# Sensor_Decoderv0_6.net
KiCad netlist of a schematic drawn in EAGLE
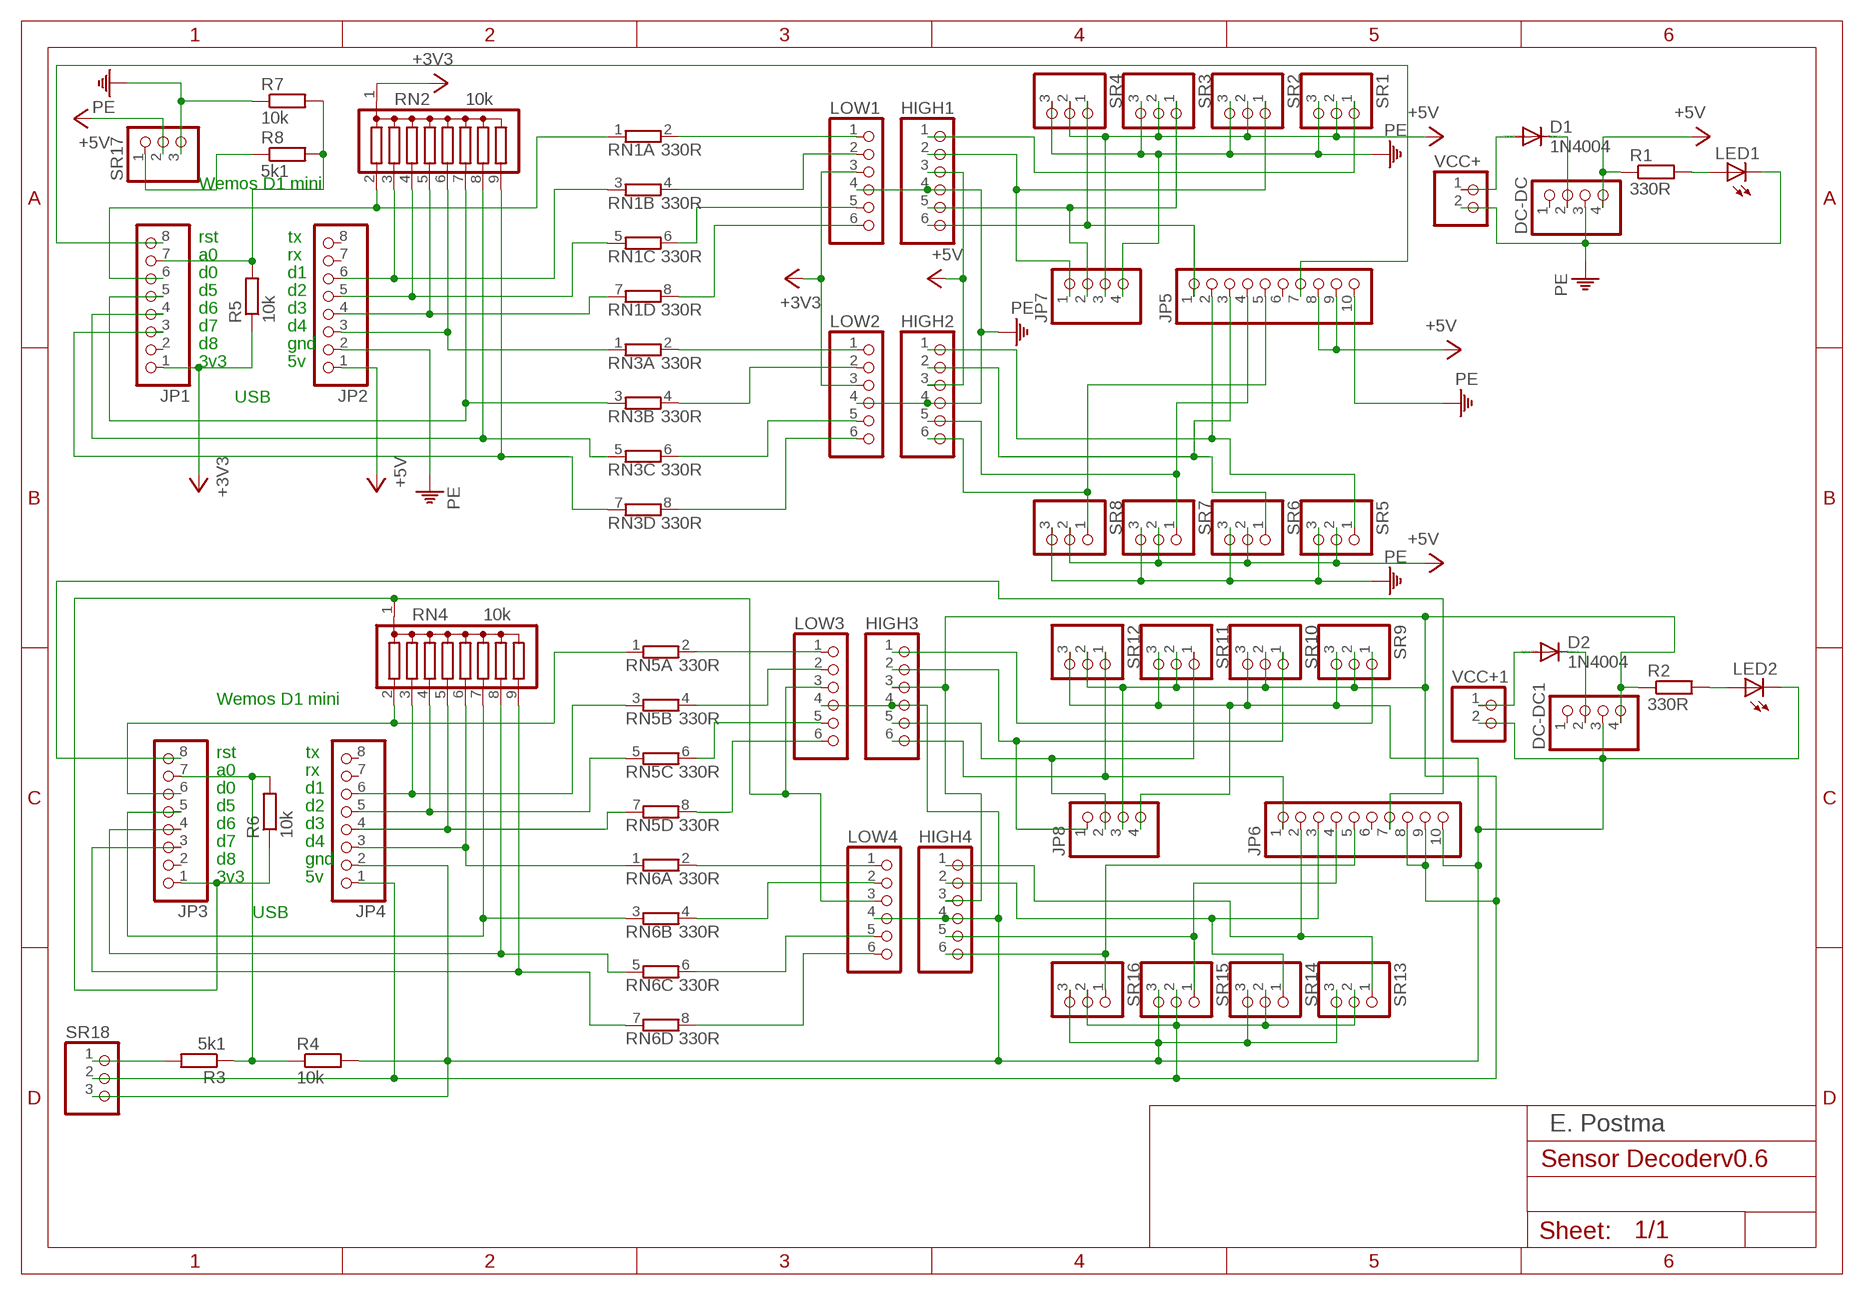
[diagram p0: schematic, sheet 1]

(export (version "E")
  (design (tool "Eeschema 10.0.6"))
  (components
    (comp (ref "D1")
      (value "1N4004")
      (footprint "eagle-import:DO41-10")
      (libsource (lib "eagle-import") (part "1N4004"))
    )
    (comp (ref "D2")
      (value "1N4004")
      (footprint "eagle-import:DO41-10")
      (libsource (lib "eagle-import") (part "1N4004"))
    )
    (comp (ref "DC-DC")
      (value "PINHD-1X4")
      (footprint "eagle-import:1X04")
      (libsource (lib "eagle-import") (part "PINHD-1X4"))
    )
    (comp (ref "DC-DC1")
      (value "PINHD-1X4")
      (footprint "eagle-import:1X04")
      (libsource (lib "eagle-import") (part "PINHD-1X4"))
    )
    (comp (ref "HIGH1")
      (value "PINHD-1X6")
      (footprint "eagle-import:1X06")
      (libsource (lib "eagle-import") (part "PINHD-1X6"))
    )
    (comp (ref "HIGH2")
      (value "PINHD-1X6")
      (footprint "eagle-import:1X06")
      (libsource (lib "eagle-import") (part "PINHD-1X6"))
    )
    (comp (ref "HIGH3")
      (value "PINHD-1X6")
      (footprint "eagle-import:1X06")
      (libsource (lib "eagle-import") (part "PINHD-1X6"))
    )
    (comp (ref "HIGH4")
      (value "PINHD-1X6")
      (footprint "eagle-import:1X06")
      (libsource (lib "eagle-import") (part "PINHD-1X6"))
    )
    (comp (ref "JP1")
      (value "PINHD-1X8")
      (footprint "eagle-import:1X08")
      (libsource (lib "eagle-import") (part "PINHD-1X8"))
    )
    (comp (ref "JP2")
      (value "PINHD-1X8")
      (footprint "eagle-import:1X08")
      (libsource (lib "eagle-import") (part "PINHD-1X8"))
    )
    (comp (ref "JP3")
      (value "PINHD-1X8")
      (footprint "eagle-import:1X08")
      (libsource (lib "eagle-import") (part "PINHD-1X8"))
    )
    (comp (ref "JP4")
      (value "PINHD-1X8")
      (footprint "eagle-import:1X08")
      (libsource (lib "eagle-import") (part "PINHD-1X8"))
    )
    (comp (ref "JP5")
      (value "PINHD-1X10")
      (footprint "eagle-import:1X10")
      (libsource (lib "eagle-import") (part "PINHD-1X10"))
    )
    (comp (ref "JP6")
      (value "PINHD-1X10")
      (footprint "eagle-import:1X10")
      (libsource (lib "eagle-import") (part "PINHD-1X10"))
    )
    (comp (ref "JP7")
      (value "PINHD-1X4")
      (footprint "eagle-import:1X04")
      (libsource (lib "eagle-import") (part "pinhead_325_PINHD-1X4"))
    )
    (comp (ref "JP8")
      (value "PINHD-1X4")
      (footprint "eagle-import:1X04")
      (libsource (lib "eagle-import") (part "pinhead_325_PINHD-1X4"))
    )
    (comp (ref "LED1")
      (value "LED3MM")
      (footprint "eagle-import:LED3MM")
      (libsource (lib "eagle-import") (part "LED3MM"))
    )
    (comp (ref "LED2")
      (value "LED3MM")
      (footprint "eagle-import:LED3MM")
      (libsource (lib "eagle-import") (part "LED3MM"))
    )
    (comp (ref "LOW1")
      (value "PINHD-1X6")
      (footprint "eagle-import:1X06")
      (libsource (lib "eagle-import") (part "PINHD-1X6"))
    )
    (comp (ref "LOW2")
      (value "PINHD-1X6")
      (footprint "eagle-import:1X06")
      (libsource (lib "eagle-import") (part "PINHD-1X6"))
    )
    (comp (ref "LOW3")
      (value "PINHD-1X6")
      (footprint "eagle-import:1X06")
      (libsource (lib "eagle-import") (part "PINHD-1X6"))
    )
    (comp (ref "LOW4")
      (value "PINHD-1X6")
      (footprint "eagle-import:1X06")
      (libsource (lib "eagle-import") (part "PINHD-1X6"))
    )
    (comp (ref "R1")
      (value "330R")
      (footprint "eagle-import:0207_7")
      (libsource (lib "eagle-import") (part "R-EU_0207/7"))
    )
    (comp (ref "R2")
      (value "330R")
      (footprint "eagle-import:0207_7")
      (libsource (lib "eagle-import") (part "R-EU_0207/7"))
    )
    (comp (ref "R3")
      (value "5k1")
      (footprint "eagle-import:0207_7")
      (libsource (lib "eagle-import") (part "R-EU_0207/7"))
    )
    (comp (ref "R4")
      (value "10k")
      (footprint "eagle-import:0207_7")
      (libsource (lib "eagle-import") (part "R-EU_0207/7"))
    )
    (comp (ref "R5")
      (value "10k")
      (footprint "eagle-import:0207_7")
      (libsource (lib "eagle-import") (part "R-EU_0207/7"))
    )
    (comp (ref "R6")
      (value "10k")
      (footprint "eagle-import:0207_7")
      (libsource (lib "eagle-import") (part "R-EU_0207/7"))
    )
    (comp (ref "R7")
      (value "10k")
      (footprint "eagle-import:0207_7")
      (libsource (lib "eagle-import") (part "R-EU_0207/7"))
    )
    (comp (ref "R8")
      (value "5k1")
      (footprint "eagle-import:0207_7")
      (libsource (lib "eagle-import") (part "R-EU_0207/7"))
    )
    (comp (ref "RN1")
      (value "330R")
      (footprint "eagle-import:SIL8")
      (libsource (lib "eagle-import") (part "E4R"))
    )
    (comp (ref "RN2")
      (value "10k")
      (footprint "eagle-import:SIL9")
      (libsource (lib "eagle-import") (part "G08R"))
    )
    (comp (ref "RN3")
      (value "330R")
      (footprint "eagle-import:SIL8")
      (libsource (lib "eagle-import") (part "E4R"))
    )
    (comp (ref "RN4")
      (value "10k")
      (footprint "eagle-import:SIL9")
      (libsource (lib "eagle-import") (part "G08R"))
    )
    (comp (ref "RN5")
      (value "330R")
      (footprint "eagle-import:SIL8")
      (libsource (lib "eagle-import") (part "E4R"))
    )
    (comp (ref "RN6")
      (value "330R")
      (footprint "eagle-import:SIL8")
      (libsource (lib "eagle-import") (part "E4R"))
    )
    (comp (ref "SR1")
      (value "PINHD-1X3")
      (footprint "eagle-import:1X03")
      (libsource (lib "eagle-import") (part "PINHD-1X3"))
    )
    (comp (ref "SR2")
      (value "PINHD-1X3")
      (footprint "eagle-import:1X03")
      (libsource (lib "eagle-import") (part "PINHD-1X3"))
    )
    (comp (ref "SR3")
      (value "PINHD-1X3")
      (footprint "eagle-import:1X03")
      (libsource (lib "eagle-import") (part "PINHD-1X3"))
    )
    (comp (ref "SR4")
      (value "PINHD-1X3")
      (footprint "eagle-import:1X03")
      (libsource (lib "eagle-import") (part "PINHD-1X3"))
    )
    (comp (ref "SR5")
      (value "PINHD-1X3")
      (footprint "eagle-import:1X03")
      (libsource (lib "eagle-import") (part "PINHD-1X3"))
    )
    (comp (ref "SR6")
      (value "PINHD-1X3")
      (footprint "eagle-import:1X03")
      (libsource (lib "eagle-import") (part "PINHD-1X3"))
    )
    (comp (ref "SR7")
      (value "PINHD-1X3")
      (footprint "eagle-import:1X03")
      (libsource (lib "eagle-import") (part "PINHD-1X3"))
    )
    (comp (ref "SR8")
      (value "PINHD-1X3")
      (footprint "eagle-import:1X03")
      (libsource (lib "eagle-import") (part "PINHD-1X3"))
    )
    (comp (ref "SR9")
      (value "PINHD-1X3")
      (footprint "eagle-import:1X03")
      (libsource (lib "eagle-import") (part "PINHD-1X3"))
    )
    (comp (ref "SR10")
      (value "PINHD-1X3")
      (footprint "eagle-import:1X03")
      (libsource (lib "eagle-import") (part "PINHD-1X3"))
    )
    (comp (ref "SR11")
      (value "PINHD-1X3")
      (footprint "eagle-import:1X03")
      (libsource (lib "eagle-import") (part "PINHD-1X3"))
    )
    (comp (ref "SR12")
      (value "PINHD-1X3")
      (footprint "eagle-import:1X03")
      (libsource (lib "eagle-import") (part "PINHD-1X3"))
    )
    (comp (ref "SR13")
      (value "PINHD-1X3")
      (footprint "eagle-import:1X03")
      (libsource (lib "eagle-import") (part "PINHD-1X3"))
    )
    (comp (ref "SR14")
      (value "PINHD-1X3")
      (footprint "eagle-import:1X03")
      (libsource (lib "eagle-import") (part "PINHD-1X3"))
    )
    (comp (ref "SR15")
      (value "PINHD-1X3")
      (footprint "eagle-import:1X03")
      (libsource (lib "eagle-import") (part "PINHD-1X3"))
    )
    (comp (ref "SR16")
      (value "PINHD-1X3")
      (footprint "eagle-import:1X03")
      (libsource (lib "eagle-import") (part "PINHD-1X3"))
    )
    (comp (ref "SR17")
      (value "PINHD-1X3")
      (footprint "eagle-import:1X03")
      (libsource (lib "eagle-import") (part "PINHD-1X3"))
    )
    (comp (ref "SR18")
      (value "PINHD-1X3")
      (footprint "eagle-import:1X03")
      (libsource (lib "eagle-import") (part "PINHD-1X3"))
    )
    (comp (ref "VCC+")
      (value "PINHD-1X2")
      (footprint "eagle-import:1X02")
      (libsource (lib "eagle-import") (part "PINHD-1X2"))
    )
    (comp (ref "VCC+1")
      (value "PINHD-1X2")
      (footprint "eagle-import:1X02")
      (libsource (lib "eagle-import") (part "PINHD-1X2"))
    )
  )
  (nets
    (net (code "1") (name "+3V3") (class "Default")
      (node (ref "JP1") (pin "1") (pinfunction "1_1") (pintype "passive"))
      (node (ref "LOW1") (pin "3") (pinfunction "3_3") (pintype "passive"))
      (node (ref "LOW2") (pin "3") (pinfunction "3_3") (pintype "passive"))
      (node (ref "R5") (pin "1") (pinfunction "1_1") (pintype "passive"))
      (node (ref "RN2") (pin "1") (pinfunction "1_1") (pintype "passive"))
    )
    (net (code "2") (name "+5V") (class "Default")
      (node (ref "DC-DC") (pin "4") (pinfunction "4_4") (pintype "passive"))
      (node (ref "HIGH1") (pin "3") (pinfunction "3_3") (pintype "passive"))
      (node (ref "HIGH2") (pin "3") (pinfunction "3_3") (pintype "passive"))
      (node (ref "JP2") (pin "1") (pinfunction "1_1") (pintype "passive"))
      (node (ref "JP5") (pin "8") (pinfunction "8_8") (pintype "passive"))
      (node (ref "JP5") (pin "9") (pinfunction "9_9") (pintype "passive"))
      (node (ref "JP7") (pin "3") (pinfunction "3_3") (pintype "passive"))
      (node (ref "R1") (pin "1") (pinfunction "1_1") (pintype "passive"))
      (node (ref "SR1") (pin "2") (pinfunction "2_2") (pintype "passive"))
      (node (ref "SR17") (pin "2") (pinfunction "2_2") (pintype "passive"))
      (node (ref "SR2") (pin "2") (pinfunction "2_2") (pintype "passive"))
      (node (ref "SR3") (pin "2") (pinfunction "2_2") (pintype "passive"))
      (node (ref "SR4") (pin "2") (pinfunction "2_2") (pintype "passive"))
      (node (ref "SR5") (pin "2") (pinfunction "2_2") (pintype "passive"))
      (node (ref "SR6") (pin "2") (pinfunction "2_2") (pintype "passive"))
      (node (ref "SR7") (pin "2") (pinfunction "2_2") (pintype "passive"))
      (node (ref "SR8") (pin "2") (pinfunction "2_2") (pintype "passive"))
    )
    (net (code "3") (name "Net-(D1-PadA)") (class "Default")
      (node (ref "D1") (pin "A") (pinfunction "A_A") (pintype "passive"))
      (node (ref "VCC+") (pin "1") (pinfunction "1_1") (pintype "passive"))
    )
    (net (code "4") (name "Net-(D1-PadC)") (class "Default")
      (node (ref "D1") (pin "C") (pinfunction "C_C") (pintype "passive"))
      (node (ref "DC-DC") (pin "2") (pinfunction "2_2") (pintype "passive"))
    )
    (net (code "5") (name "Net-(D2-PadA)") (class "Default")
      (node (ref "D2") (pin "A") (pinfunction "A_A") (pintype "passive"))
      (node (ref "VCC+1") (pin "1") (pinfunction "1_1") (pintype "passive"))
    )
    (net (code "6") (name "Net-(D2-PadC)") (class "Default")
      (node (ref "D2") (pin "C") (pinfunction "C_C") (pintype "passive"))
      (node (ref "DC-DC1") (pin "2") (pinfunction "2_2") (pintype "passive"))
    )
    (net (code "7") (name "Net-(DC-DC1-Pad4)") (class "Default")
      (node (ref "DC-DC1") (pin "4") (pinfunction "4_4") (pintype "passive"))
      (node (ref "HIGH3") (pin "3") (pinfunction "3_3") (pintype "passive"))
      (node (ref "HIGH4") (pin "3") (pinfunction "3_3") (pintype "passive"))
      (node (ref "JP4") (pin "1") (pinfunction "1_1") (pintype "passive"))
      (node (ref "JP6") (pin "8") (pinfunction "8_8") (pintype "passive"))
      (node (ref "JP6") (pin "9") (pinfunction "9_9") (pintype "passive"))
      (node (ref "JP8") (pin "3") (pinfunction "3_3") (pintype "passive"))
      (node (ref "R2") (pin "1") (pinfunction "1_1") (pintype "passive"))
      (node (ref "SR10") (pin "2") (pinfunction "2_2") (pintype "passive"))
      (node (ref "SR11") (pin "2") (pinfunction "2_2") (pintype "passive"))
      (node (ref "SR12") (pin "2") (pinfunction "2_2") (pintype "passive"))
      (node (ref "SR13") (pin "2") (pinfunction "2_2") (pintype "passive"))
      (node (ref "SR14") (pin "2") (pinfunction "2_2") (pintype "passive"))
      (node (ref "SR15") (pin "2") (pinfunction "2_2") (pintype "passive"))
      (node (ref "SR16") (pin "2") (pinfunction "2_2") (pintype "passive"))
      (node (ref "SR18") (pin "2") (pinfunction "2_2") (pintype "passive"))
      (node (ref "SR9") (pin "2") (pinfunction "2_2") (pintype "passive"))
    )
    (net (code "8") (name "Net-(HIGH1-Pad1)") (class "Default")
      (node (ref "HIGH1") (pin "1") (pinfunction "1_1") (pintype "passive"))
      (node (ref "SR1") (pin "1") (pinfunction "1_1") (pintype "passive"))
    )
    (net (code "9") (name "Net-(HIGH1-Pad2)") (class "Default")
      (node (ref "HIGH1") (pin "2") (pinfunction "2_2") (pintype "passive"))
      (node (ref "JP7") (pin "1") (pinfunction "1_1") (pintype "passive"))
      (node (ref "SR2") (pin "1") (pinfunction "1_1") (pintype "passive"))
    )
    (net (code "10") (name "Net-(HIGH1-Pad5)") (class "Default")
      (node (ref "HIGH1") (pin "5") (pinfunction "5_5") (pintype "passive"))
      (node (ref "JP7") (pin "2") (pinfunction "2_2") (pintype "passive"))
      (node (ref "SR3") (pin "1") (pinfunction "1_1") (pintype "passive"))
    )
    (net (code "11") (name "Net-(HIGH1-Pad6)") (class "Default")
      (node (ref "HIGH1") (pin "6") (pinfunction "6_6") (pintype "passive"))
      (node (ref "JP5") (pin "1") (pinfunction "1_1") (pintype "passive"))
      (node (ref "SR4") (pin "1") (pinfunction "1_1") (pintype "passive"))
    )
    (net (code "12") (name "Net-(HIGH2-Pad1)") (class "Default")
      (node (ref "HIGH2") (pin "1") (pinfunction "1_1") (pintype "passive"))
      (node (ref "JP5") (pin "2") (pinfunction "2_2") (pintype "passive"))
      (node (ref "SR5") (pin "1") (pinfunction "1_1") (pintype "passive"))
    )
    (net (code "13") (name "Net-(HIGH2-Pad2)") (class "Default")
      (node (ref "HIGH2") (pin "2") (pinfunction "2_2") (pintype "passive"))
      (node (ref "JP5") (pin "3") (pinfunction "3_3") (pintype "passive"))
      (node (ref "SR6") (pin "1") (pinfunction "1_1") (pintype "passive"))
    )
    (net (code "14") (name "Net-(HIGH2-Pad5)") (class "Default")
      (node (ref "HIGH2") (pin "5") (pinfunction "5_5") (pintype "passive"))
      (node (ref "JP5") (pin "4") (pinfunction "4_4") (pintype "passive"))
      (node (ref "SR7") (pin "1") (pinfunction "1_1") (pintype "passive"))
    )
    (net (code "15") (name "Net-(HIGH2-Pad6)") (class "Default")
      (node (ref "HIGH2") (pin "6") (pinfunction "6_6") (pintype "passive"))
      (node (ref "JP5") (pin "5") (pinfunction "5_5") (pintype "passive"))
      (node (ref "SR8") (pin "1") (pinfunction "1_1") (pintype "passive"))
    )
    (net (code "16") (name "Net-(HIGH3-Pad1)") (class "Default")
      (node (ref "HIGH3") (pin "1") (pinfunction "1_1") (pintype "passive"))
      (node (ref "SR9") (pin "1") (pinfunction "1_1") (pintype "passive"))
    )
    (net (code "17") (name "Net-(HIGH3-Pad2)") (class "Default")
      (node (ref "HIGH3") (pin "2") (pinfunction "2_2") (pintype "passive"))
      (node (ref "JP8") (pin "1") (pinfunction "1_1") (pintype "passive"))
      (node (ref "SR10") (pin "1") (pinfunction "1_1") (pintype "passive"))
    )
    (net (code "18") (name "Net-(HIGH3-Pad5)") (class "Default")
      (node (ref "HIGH3") (pin "5") (pinfunction "5_5") (pintype "passive"))
      (node (ref "JP8") (pin "2") (pinfunction "2_2") (pintype "passive"))
      (node (ref "SR11") (pin "1") (pinfunction "1_1") (pintype "passive"))
    )
    (net (code "19") (name "Net-(HIGH3-Pad6)") (class "Default")
      (node (ref "HIGH3") (pin "6") (pinfunction "6_6") (pintype "passive"))
      (node (ref "JP6") (pin "1") (pinfunction "1_1") (pintype "passive"))
      (node (ref "SR12") (pin "1") (pinfunction "1_1") (pintype "passive"))
    )
    (net (code "20") (name "Net-(HIGH4-Pad1)") (class "Default")
      (node (ref "HIGH4") (pin "1") (pinfunction "1_1") (pintype "passive"))
      (node (ref "JP6") (pin "2") (pinfunction "2_2") (pintype "passive"))
      (node (ref "SR13") (pin "1") (pinfunction "1_1") (pintype "passive"))
    )
    (net (code "21") (name "Net-(HIGH4-Pad2)") (class "Default")
      (node (ref "HIGH4") (pin "2") (pinfunction "2_2") (pintype "passive"))
      (node (ref "JP6") (pin "3") (pinfunction "3_3") (pintype "passive"))
      (node (ref "SR14") (pin "1") (pinfunction "1_1") (pintype "passive"))
    )
    (net (code "22") (name "Net-(HIGH4-Pad5)") (class "Default")
      (node (ref "HIGH4") (pin "5") (pinfunction "5_5") (pintype "passive"))
      (node (ref "JP6") (pin "4") (pinfunction "4_4") (pintype "passive"))
      (node (ref "SR15") (pin "1") (pinfunction "1_1") (pintype "passive"))
    )
    (net (code "23") (name "Net-(HIGH4-Pad6)") (class "Default")
      (node (ref "HIGH4") (pin "6") (pinfunction "6_6") (pintype "passive"))
      (node (ref "JP6") (pin "5") (pinfunction "5_5") (pintype "passive"))
      (node (ref "SR16") (pin "1") (pinfunction "1_1") (pintype "passive"))
    )
    (net (code "24") (name "Net-(JP1-Pad6)") (class "Default")
      (node (ref "JP1") (pin "6") (pinfunction "6_6") (pintype "passive"))
      (node (ref "RN1") (pin "1") (pinfunction "1_1") (pintype "passive"))
      (node (ref "RN2") (pin "2") (pinfunction "2_2") (pintype "passive"))
    )
    (net (code "25") (name "Net-(JP1-Pad7)") (class "Default")
      (node (ref "JP1") (pin "7") (pinfunction "7_7") (pintype "passive"))
      (node (ref "R5") (pin "2") (pinfunction "2_2") (pintype "passive"))
      (node (ref "R7") (pin "2") (pinfunction "2_2") (pintype "passive"))
      (node (ref "R8") (pin "2") (pinfunction "2_2") (pintype "passive"))
    )
    (net (code "26") (name "Net-(JP1-Pad8)") (class "Default")
      (node (ref "JP1") (pin "8") (pinfunction "8_8") (pintype "passive"))
      (node (ref "JP5") (pin "7") (pinfunction "7_7") (pintype "passive"))
    )
    (net (code "27") (name "Net-(JP2-Pad3)") (class "Default")
      (node (ref "JP2") (pin "3") (pinfunction "3_3") (pintype "passive"))
      (node (ref "RN2") (pin "6") (pinfunction "6_6") (pintype "passive"))
      (node (ref "RN3") (pin "1") (pinfunction "1_1") (pintype "passive"))
    )
    (net (code "28") (name "Net-(JP3-Pad1)") (class "Default")
      (node (ref "JP3") (pin "1") (pinfunction "1_1") (pintype "passive"))
      (node (ref "LOW3") (pin "3") (pinfunction "3_3") (pintype "passive"))
      (node (ref "LOW4") (pin "3") (pinfunction "3_3") (pintype "passive"))
      (node (ref "R6") (pin "1") (pinfunction "1_1") (pintype "passive"))
      (node (ref "RN4") (pin "1") (pinfunction "1_1") (pintype "passive"))
    )
    (net (code "29") (name "Net-(JP3-Pad6)") (class "Default")
      (node (ref "JP3") (pin "6") (pinfunction "6_6") (pintype "passive"))
      (node (ref "RN4") (pin "2") (pinfunction "2_2") (pintype "passive"))
      (node (ref "RN5") (pin "1") (pinfunction "1_1") (pintype "passive"))
    )
    (net (code "30") (name "Net-(JP3-Pad7)") (class "Default")
      (node (ref "JP3") (pin "7") (pinfunction "7_7") (pintype "passive"))
      (node (ref "R3") (pin "1") (pinfunction "1_1") (pintype "passive"))
      (node (ref "R4") (pin "1") (pinfunction "1_1") (pintype "passive"))
      (node (ref "R6") (pin "2") (pinfunction "2_2") (pintype "passive"))
    )
    (net (code "31") (name "Net-(JP3-Pad8)") (class "Default")
      (node (ref "JP3") (pin "8") (pinfunction "8_8") (pintype "passive"))
      (node (ref "JP6") (pin "7") (pinfunction "7_7") (pintype "passive"))
    )
    (net (code "32") (name "Net-(JP4-Pad3)") (class "Default")
      (node (ref "JP4") (pin "3") (pinfunction "3_3") (pintype "passive"))
      (node (ref "RN4") (pin "6") (pinfunction "6_6") (pintype "passive"))
      (node (ref "RN6") (pin "1") (pinfunction "1_1") (pintype "passive"))
    )
    (net (code "33") (name "Net-(LED1-PadA)") (class "Default")
      (node (ref "LED1") (pin "A") (pinfunction "A_A") (pintype "passive"))
      (node (ref "R1") (pin "2") (pinfunction "2_2") (pintype "passive"))
    )
    (net (code "34") (name "Net-(LED2-C)") (class "Default")
      (node (ref "DC-DC1") (pin "3") (pinfunction "3_3") (pintype "passive"))
      (node (ref "HIGH3") (pin "4") (pinfunction "4_4") (pintype "passive"))
      (node (ref "HIGH4") (pin "4") (pinfunction "4_4") (pintype "passive"))
      (node (ref "JP4") (pin "2") (pinfunction "2_2") (pintype "passive"))
      (node (ref "JP6") (pin "10") (pinfunction "10_10") (pintype "passive"))
      (node (ref "JP8") (pin "4") (pinfunction "4_4") (pintype "passive"))
      (node (ref "LED2") (pin "K") (pinfunction "C_K") (pintype "passive"))
      (node (ref "LOW3") (pin "4") (pinfunction "4_4") (pintype "passive"))
      (node (ref "LOW4") (pin "4") (pinfunction "4_4") (pintype "passive"))
      (node (ref "R4") (pin "2") (pinfunction "2_2") (pintype "passive"))
      (node (ref "SR10") (pin "3") (pinfunction "3_3") (pintype "passive"))
      (node (ref "SR11") (pin "3") (pinfunction "3_3") (pintype "passive"))
      (node (ref "SR12") (pin "3") (pinfunction "3_3") (pintype "passive"))
      (node (ref "SR13") (pin "3") (pinfunction "3_3") (pintype "passive"))
      (node (ref "SR14") (pin "3") (pinfunction "3_3") (pintype "passive"))
      (node (ref "SR15") (pin "3") (pinfunction "3_3") (pintype "passive"))
      (node (ref "SR16") (pin "3") (pinfunction "3_3") (pintype "passive"))
      (node (ref "SR18") (pin "3") (pinfunction "3_3") (pintype "passive"))
      (node (ref "SR9") (pin "3") (pinfunction "3_3") (pintype "passive"))
      (node (ref "VCC+1") (pin "2") (pinfunction "2_2") (pintype "passive"))
    )
    (net (code "35") (name "Net-(LED2-PadA)") (class "Default")
      (node (ref "LED2") (pin "A") (pinfunction "A_A") (pintype "passive"))
      (node (ref "R2") (pin "2") (pinfunction "2_2") (pintype "passive"))
    )
    (net (code "36") (name "Net-(LOW1-Pad1)") (class "Default")
      (node (ref "LOW1") (pin "1") (pinfunction "1_1") (pintype "passive"))
      (node (ref "RN1") (pin "2") (pinfunction "2_2") (pintype "passive"))
    )
    (net (code "37") (name "Net-(LOW2-Pad1)") (class "Default")
      (node (ref "LOW2") (pin "1") (pinfunction "1_1") (pintype "passive"))
      (node (ref "RN3") (pin "2") (pinfunction "2_2") (pintype "passive"))
    )
    (net (code "38") (name "Net-(LOW3-Pad1)") (class "Default")
      (node (ref "LOW3") (pin "1") (pinfunction "1_1") (pintype "passive"))
      (node (ref "RN5") (pin "2") (pinfunction "2_2") (pintype "passive"))
    )
    (net (code "39") (name "Net-(LOW4-Pad1)") (class "Default")
      (node (ref "LOW4") (pin "1") (pinfunction "1_1") (pintype "passive"))
      (node (ref "RN6") (pin "2") (pinfunction "2_2") (pintype "passive"))
    )
    (net (code "40") (name "Net-(R3-Pad2)") (class "Default")
      (node (ref "R3") (pin "2") (pinfunction "2_2") (pintype "passive"))
      (node (ref "SR18") (pin "1") (pinfunction "1_1") (pintype "passive"))
    )
    (net (code "41") (name "Net-(R8-Pad1)") (class "Default")
      (node (ref "R8") (pin "1") (pinfunction "1_1") (pintype "passive"))
      (node (ref "SR17") (pin "1") (pinfunction "1_1") (pintype "passive"))
    )
    (net (code "42") (name "Net-(RN1B-1)") (class "Default")
      (node (ref "JP2") (pin "6") (pinfunction "6_6") (pintype "passive"))
      (node (ref "RN1") (pin "3") (pinfunction "1_3") (pintype "passive"))
      (node (ref "RN2") (pin "3") (pinfunction "3_3") (pintype "passive"))
    )
    (net (code "43") (name "Net-(RN1B-2)") (class "Default")
      (node (ref "LOW1") (pin "2") (pinfunction "2_2") (pintype "passive"))
      (node (ref "RN1") (pin "4") (pinfunction "2_4") (pintype "passive"))
    )
    (net (code "44") (name "Net-(RN1C-1)") (class "Default")
      (node (ref "JP2") (pin "5") (pinfunction "5_5") (pintype "passive"))
      (node (ref "RN1") (pin "5") (pinfunction "1_5") (pintype "passive"))
      (node (ref "RN2") (pin "4") (pinfunction "4_4") (pintype "passive"))
    )
    (net (code "45") (name "Net-(RN1C-2)") (class "Default")
      (node (ref "LOW1") (pin "5") (pinfunction "5_5") (pintype "passive"))
      (node (ref "RN1") (pin "6") (pinfunction "2_6") (pintype "passive"))
    )
    (net (code "46") (name "Net-(RN1D-1)") (class "Default")
      (node (ref "JP2") (pin "4") (pinfunction "4_4") (pintype "passive"))
      (node (ref "RN1") (pin "7") (pinfunction "1_7") (pintype "passive"))
      (node (ref "RN2") (pin "5") (pinfunction "5_5") (pintype "passive"))
    )
    (net (code "47") (name "Net-(RN1D-2)") (class "Default")
      (node (ref "LOW1") (pin "6") (pinfunction "6_6") (pintype "passive"))
      (node (ref "RN1") (pin "8") (pinfunction "2_8") (pintype "passive"))
    )
    (net (code "48") (name "Net-(RN3B-1)") (class "Default")
      (node (ref "JP1") (pin "5") (pinfunction "5_5") (pintype "passive"))
      (node (ref "RN2") (pin "7") (pinfunction "7_7") (pintype "passive"))
      (node (ref "RN3") (pin "3") (pinfunction "1_3") (pintype "passive"))
    )
    (net (code "49") (name "Net-(RN3B-2)") (class "Default")
      (node (ref "LOW2") (pin "2") (pinfunction "2_2") (pintype "passive"))
      (node (ref "RN3") (pin "4") (pinfunction "2_4") (pintype "passive"))
    )
    (net (code "50") (name "Net-(RN3C-1)") (class "Default")
      (node (ref "JP1") (pin "4") (pinfunction "4_4") (pintype "passive"))
      (node (ref "RN2") (pin "8") (pinfunction "8_8") (pintype "passive"))
      (node (ref "RN3") (pin "5") (pinfunction "1_5") (pintype "passive"))
    )
    (net (code "51") (name "Net-(RN3C-2)") (class "Default")
      (node (ref "LOW2") (pin "5") (pinfunction "5_5") (pintype "passive"))
      (node (ref "RN3") (pin "6") (pinfunction "2_6") (pintype "passive"))
    )
    (net (code "52") (name "Net-(RN3D-1)") (class "Default")
      (node (ref "JP1") (pin "3") (pinfunction "3_3") (pintype "passive"))
      (node (ref "RN2") (pin "9") (pinfunction "9_9") (pintype "passive"))
      (node (ref "RN3") (pin "7") (pinfunction "1_7") (pintype "passive"))
    )
    (net (code "53") (name "Net-(RN3D-2)") (class "Default")
      (node (ref "LOW2") (pin "6") (pinfunction "6_6") (pintype "passive"))
      (node (ref "RN3") (pin "8") (pinfunction "2_8") (pintype "passive"))
    )
    (net (code "54") (name "Net-(RN5B-1)") (class "Default")
      (node (ref "JP4") (pin "6") (pinfunction "6_6") (pintype "passive"))
      (node (ref "RN4") (pin "3") (pinfunction "3_3") (pintype "passive"))
      (node (ref "RN5") (pin "3") (pinfunction "1_3") (pintype "passive"))
    )
    (net (code "55") (name "Net-(RN5B-2)") (class "Default")
      (node (ref "LOW3") (pin "2") (pinfunction "2_2") (pintype "passive"))
      (node (ref "RN5") (pin "4") (pinfunction "2_4") (pintype "passive"))
    )
    (net (code "56") (name "Net-(RN5C-1)") (class "Default")
      (node (ref "JP4") (pin "5") (pinfunction "5_5") (pintype "passive"))
      (node (ref "RN4") (pin "4") (pinfunction "4_4") (pintype "passive"))
      (node (ref "RN5") (pin "5") (pinfunction "1_5") (pintype "passive"))
    )
    (net (code "57") (name "Net-(RN5C-2)") (class "Default")
      (node (ref "LOW3") (pin "5") (pinfunction "5_5") (pintype "passive"))
      (node (ref "RN5") (pin "6") (pinfunction "2_6") (pintype "passive"))
    )
    (net (code "58") (name "Net-(RN5D-1)") (class "Default")
      (node (ref "JP4") (pin "4") (pinfunction "4_4") (pintype "passive"))
      (node (ref "RN4") (pin "5") (pinfunction "5_5") (pintype "passive"))
      (node (ref "RN5") (pin "7") (pinfunction "1_7") (pintype "passive"))
    )
    (net (code "59") (name "Net-(RN5D-2)") (class "Default")
      (node (ref "LOW3") (pin "6") (pinfunction "6_6") (pintype "passive"))
      (node (ref "RN5") (pin "8") (pinfunction "2_8") (pintype "passive"))
    )
    (net (code "60") (name "Net-(RN6B-1)") (class "Default")
      (node (ref "JP3") (pin "5") (pinfunction "5_5") (pintype "passive"))
      (node (ref "RN4") (pin "7") (pinfunction "7_7") (pintype "passive"))
      (node (ref "RN6") (pin "3") (pinfunction "1_3") (pintype "passive"))
    )
    (net (code "61") (name "Net-(RN6B-2)") (class "Default")
      (node (ref "LOW4") (pin "2") (pinfunction "2_2") (pintype "passive"))
      (node (ref "RN6") (pin "4") (pinfunction "2_4") (pintype "passive"))
    )
    (net (code "62") (name "Net-(RN6C-1)") (class "Default")
      (node (ref "JP3") (pin "4") (pinfunction "4_4") (pintype "passive"))
      (node (ref "RN4") (pin "8") (pinfunction "8_8") (pintype "passive"))
      (node (ref "RN6") (pin "5") (pinfunction "1_5") (pintype "passive"))
    )
    (net (code "63") (name "Net-(RN6C-2)") (class "Default")
      (node (ref "LOW4") (pin "5") (pinfunction "5_5") (pintype "passive"))
      (node (ref "RN6") (pin "6") (pinfunction "2_6") (pintype "passive"))
    )
    (net (code "64") (name "Net-(RN6D-1)") (class "Default")
      (node (ref "JP3") (pin "3") (pinfunction "3_3") (pintype "passive"))
      (node (ref "RN4") (pin "9") (pinfunction "9_9") (pintype "passive"))
      (node (ref "RN6") (pin "7") (pinfunction "1_7") (pintype "passive"))
    )
    (net (code "65") (name "Net-(RN6D-2)") (class "Default")
      (node (ref "LOW4") (pin "6") (pinfunction "6_6") (pintype "passive"))
      (node (ref "RN6") (pin "8") (pinfunction "2_8") (pintype "passive"))
    )
    (net (code "66") (name "PE") (class "Default")
      (node (ref "DC-DC") (pin "3") (pinfunction "3_3") (pintype "passive"))
      (node (ref "HIGH1") (pin "4") (pinfunction "4_4") (pintype "passive"))
      (node (ref "HIGH2") (pin "4") (pinfunction "4_4") (pintype "passive"))
      (node (ref "JP2") (pin "2") (pinfunction "2_2") (pintype "passive"))
      (node (ref "JP5") (pin "10") (pinfunction "10_10") (pintype "passive"))
      (node (ref "JP7") (pin "4") (pinfunction "4_4") (pintype "passive"))
      (node (ref "LED1") (pin "K") (pinfunction "C_K") (pintype "passive"))
      (node (ref "LOW1") (pin "4") (pinfunction "4_4") (pintype "passive"))
      (node (ref "LOW2") (pin "4") (pinfunction "4_4") (pintype "passive"))
      (node (ref "R7") (pin "1") (pinfunction "1_1") (pintype "passive"))
      (node (ref "SR1") (pin "3") (pinfunction "3_3") (pintype "passive"))
      (node (ref "SR17") (pin "3") (pinfunction "3_3") (pintype "passive"))
      (node (ref "SR2") (pin "3") (pinfunction "3_3") (pintype "passive"))
      (node (ref "SR3") (pin "3") (pinfunction "3_3") (pintype "passive"))
      (node (ref "SR4") (pin "3") (pinfunction "3_3") (pintype "passive"))
      (node (ref "SR5") (pin "3") (pinfunction "3_3") (pintype "passive"))
      (node (ref "SR6") (pin "3") (pinfunction "3_3") (pintype "passive"))
      (node (ref "SR7") (pin "3") (pinfunction "3_3") (pintype "passive"))
      (node (ref "SR8") (pin "3") (pinfunction "3_3") (pintype "passive"))
      (node (ref "VCC+") (pin "2") (pinfunction "2_2") (pintype "passive"))
    )
    (net (code "67") (name "unconnected-(DC-DC-Pad1)") (class "Default")
      (node (ref "DC-DC") (pin "1") (pinfunction "1_1") (pintype "passive"))
    )
    (net (code "68") (name "unconnected-(DC-DC1-Pad1)") (class "Default")
      (node (ref "DC-DC1") (pin "1") (pinfunction "1_1") (pintype "passive"))
    )
    (net (code "69") (name "unconnected-(JP1-Pad2)") (class "Default")
      (node (ref "JP1") (pin "2") (pinfunction "2_2") (pintype "passive"))
    )
    (net (code "70") (name "unconnected-(JP2-Pad7)") (class "Default")
      (node (ref "JP2") (pin "7") (pinfunction "7_7") (pintype "passive"))
    )
    (net (code "71") (name "unconnected-(JP2-Pad8)") (class "Default")
      (node (ref "JP2") (pin "8") (pinfunction "8_8") (pintype "passive"))
    )
    (net (code "72") (name "unconnected-(JP3-Pad2)") (class "Default")
      (node (ref "JP3") (pin "2") (pinfunction "2_2") (pintype "passive"))
    )
    (net (code "73") (name "unconnected-(JP4-Pad7)") (class "Default")
      (node (ref "JP4") (pin "7") (pinfunction "7_7") (pintype "passive"))
    )
    (net (code "74") (name "unconnected-(JP4-Pad8)") (class "Default")
      (node (ref "JP4") (pin "8") (pinfunction "8_8") (pintype "passive"))
    )
    (net (code "75") (name "unconnected-(JP5-Pad6)") (class "Default")
      (node (ref "JP5") (pin "6") (pinfunction "6_6") (pintype "passive"))
    )
    (net (code "76") (name "unconnected-(JP6-Pad6)") (class "Default")
      (node (ref "JP6") (pin "6") (pinfunction "6_6") (pintype "passive"))
    )
  )
)
